# clock.net
KiCad netlist of a schematic drawn in Altium Designer
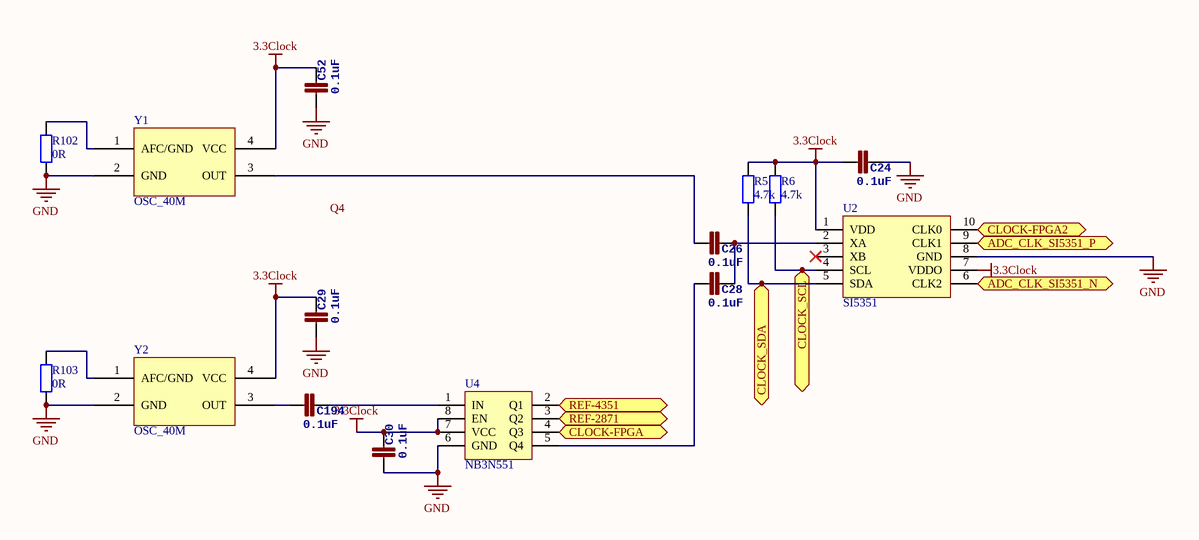
[diagram p0: clock.SchDoc]

(export (version "E")
  (design (tool "Eeschema 10.0.6"))
  (components
    (comp (ref "C24")
      (value "0.1uF")
      (footprint "0402")
      (description "<b>Capacitor</b>\nStandard 0603 ceramic capacitor, and 0.1\" leaded capacitor.")
      (fields (field (name "PARTNO") "CC0402ZRY5V7BB104"))
      (libsource (lib "pixhawk2") (part "CAP0402-CAP"))
    )
    (comp (ref "C26")
      (value "0.1uF")
      (footprint "0402")
      (description "<b>Capacitor</b>\nStandard 0603 ceramic capacitor, and 0.1\" leaded capacitor.")
      (fields (field (name "PARTNO") "CC0402ZRY5V7BB104"))
      (libsource (lib "pixhawk2") (part "CAP0402-CAP"))
    )
    (comp (ref "C28")
      (value "0.1uF")
      (footprint "0402")
      (description "<b>Capacitor</b>\nStandard 0603 ceramic capacitor, and 0.1\" leaded capacitor.")
      (fields (field (name "PARTNO") "CC0402ZRY5V7BB104"))
      (libsource (lib "pixhawk2") (part "CAP0402-CAP"))
    )
    (comp (ref "C29")
      (value "0.1uF")
      (footprint "0402")
      (description "<b>Capacitor</b>\nStandard 0603 ceramic capacitor, and 0.1\" leaded capacitor.")
      (fields (field (name "PARTNO") "CC0402ZRY5V7BB104"))
      (libsource (lib "") (part "CAP0402-CAP_1"))
    )
    (comp (ref "C30")
      (value "0.1uF")
      (footprint "0402")
      (description "<b>Capacitor</b>\nStandard 0603 ceramic capacitor, and 0.1\" leaded capacitor.")
      (fields (field (name "PARTNO") "CC0402ZRY5V7BB104"))
      (libsource (lib "") (part "CAP0402-CAP_1"))
    )
    (comp (ref "C52")
      (value "0.1uF")
      (footprint "0402")
      (description "<b>Capacitor</b>\nStandard 0603 ceramic capacitor, and 0.1\" leaded capacitor.")
      (fields (field (name "PARTNO") "CC0402ZRY5V7BB104"))
      (libsource (lib "") (part "CAP0402-CAP_1"))
    )
    (comp (ref "C194")
      (value "0.1uF")
      (footprint "0402")
      (description "<b>Capacitor</b>\nStandard 0603 ceramic capacitor, and 0.1\" leaded capacitor.")
      (fields (field (name "PARTNO") "CC0402ZRY5V7BB104"))
      (libsource (lib "pixhawk2") (part "CAP0402-CAP"))
    )
    (comp (ref "R5")
      (value "4.7k")
      (footprint "0402")
      (description "Resistor")
      (fields (field (name "PUBLISHER") "Altium Limited"))
      (libsource (lib "Miscellaneous Devices") (part "Res2"))
    )
    (comp (ref "R6")
      (value "4.7k")
      (footprint "0402")
      (description "Resistor")
      (fields (field (name "PUBLISHER") "Altium Limited"))
      (libsource (lib "Miscellaneous Devices") (part "Res2"))
    )
    (comp (ref "R102")
      (value "0R")
      (footprint "0402")
      (description "Resistor")
      (fields (field (name "PUBLISHER") "Altium Limited"))
      (libsource (lib "Miscellaneous Devices") (part "Res2"))
    )
    (comp (ref "R103")
      (value "0R")
      (footprint "0402")
      (description "Resistor")
      (fields (field (name "PUBLISHER") "Altium Limited"))
      (libsource (lib "Miscellaneous Devices") (part "Res2"))
    )
    (comp (ref "U2") (value "SI5351") (footprint "MSOP10/VSSOP10") (libsource (lib "F4SDR") (part "SI5351")))
    (comp (ref "U4") (value "NB3N551") (footprint "SO8") (libsource (lib "F4SDR") (part "NB3N551")))
    (comp (ref "Y1") (value "OSC_40M") (footprint "TXC_7Q") (libsource (lib "F4SDR") (part "OSC_40M")))
    (comp (ref "Y2") (value "OSC_40M") (footprint "TXC_7Q") (libsource (lib "F4SDR") (part "OSC_40M")))
  )
  (nets
    (net (code "1") (name "/ADC_CLK_SI5351_N") (class "Default")
      (node (ref "U2") (pin "6") (pinfunction "CLK2_6") (pintype "passive"))
    )
    (net (code "2") (name "/ADC_CLK_SI5351_P") (class "Default")
      (node (ref "U2") (pin "9") (pinfunction "CLK1_9") (pintype "passive"))
    )
    (net (code "3") (name "/CLOCK-FPGA") (class "Default")
      (node (ref "U4") (pin "4") (pinfunction "Q3_4") (pintype "passive"))
    )
    (net (code "4") (name "/CLOCK-FPGA2") (class "Default")
      (node (ref "U2") (pin "10") (pinfunction "CLK0_10") (pintype "passive"))
    )
    (net (code "5") (name "/CLOCK_SCL") (class "Default")
      (node (ref "R6") (pin "2") (pinfunction "2_2") (pintype "passive"))
      (node (ref "U2") (pin "4") (pinfunction "SCL_4") (pintype "passive"))
    )
    (net (code "6") (name "/CLOCK_SDA") (class "Default")
      (node (ref "R5") (pin "2") (pinfunction "2_2") (pintype "passive"))
      (node (ref "U2") (pin "5") (pinfunction "SDA_5") (pintype "passive"))
    )
    (net (code "8") (name "/REF-2871") (class "Default")
      (node (ref "U4") (pin "3") (pinfunction "Q2_3") (pintype "passive"))
    )
    (net (code "9") (name "/REF-4351") (class "Default")
      (node (ref "U4") (pin "2") (pinfunction "Q1_2") (pintype "passive"))
    )
    (net (code "10") (name "3.3Clock") (class "Default")
      (node (ref "C24") (pin "1") (pinfunction "1_1") (pintype "passive"))
      (node (ref "C29") (pin "2") (pinfunction "2_2") (pintype "passive"))
      (node (ref "C30") (pin "2") (pinfunction "2_2") (pintype "passive"))
      (node (ref "C52") (pin "2") (pinfunction "2_2") (pintype "passive"))
      (node (ref "R5") (pin "1") (pinfunction "1_1") (pintype "passive"))
      (node (ref "R6") (pin "1") (pinfunction "1_1") (pintype "passive"))
      (node (ref "U2") (pin "1") (pinfunction "VDD_1") (pintype "passive"))
      (node (ref "U2") (pin "7") (pinfunction "VDDO_7") (pintype "passive"))
      (node (ref "U4") (pin "7") (pinfunction "VCC_7") (pintype "passive"))
      (node (ref "U4") (pin "8") (pinfunction "EN_8") (pintype "passive"))
      (node (ref "Y1") (pin "4") (pinfunction "VCC_4") (pintype "passive"))
      (node (ref "Y2") (pin "4") (pinfunction "VCC_4") (pintype "passive"))
    )
    (net (code "11") (name "GND") (class "Default")
      (node (ref "C24") (pin "2") (pinfunction "2_2") (pintype "passive"))
      (node (ref "C29") (pin "1") (pinfunction "1_1") (pintype "passive"))
      (node (ref "C30") (pin "1") (pinfunction "1_1") (pintype "passive"))
      (node (ref "C52") (pin "1") (pinfunction "1_1") (pintype "passive"))
      (node (ref "R102") (pin "2") (pinfunction "2_2") (pintype "passive"))
      (node (ref "R103") (pin "2") (pinfunction "2_2") (pintype "passive"))
      (node (ref "U2") (pin "8") (pinfunction "GND_8") (pintype "passive"))
      (node (ref "U4") (pin "6") (pinfunction "GND_6") (pintype "passive"))
      (node (ref "Y1") (pin "2") (pinfunction "GND_2") (pintype "passive"))
      (node (ref "Y2") (pin "2") (pinfunction "GND_2") (pintype "passive"))
    )
    (net (code "12") (name "Net-(U2-XA)") (class "Default")
      (node (ref "C26") (pin "2") (pinfunction "2_2") (pintype "passive"))
      (node (ref "C28") (pin "2") (pinfunction "2_2") (pintype "passive"))
      (node (ref "U2") (pin "2") (pinfunction "XA_2") (pintype "passive"))
    )
    (net (code "13") (name "Net-(U4-IN)") (class "Default")
      (node (ref "C194") (pin "2") (pinfunction "2_2") (pintype "passive"))
      (node (ref "U4") (pin "1") (pinfunction "IN_1") (pintype "passive"))
    )
    (net (code "14") (name "Net-(U4-Q4)") (class "Default")
      (node (ref "C28") (pin "1") (pinfunction "1_1") (pintype "passive"))
      (node (ref "U4") (pin "5") (pinfunction "Q4_5") (pintype "passive"))
    )
    (net (code "15") (name "Net-(Y1-AFC{slash}GND)") (class "Default")
      (node (ref "R102") (pin "1") (pinfunction "1_1") (pintype "passive"))
      (node (ref "Y1") (pin "1") (pinfunction "AFC/GND_1") (pintype "passive"))
    )
    (net (code "16") (name "Net-(Y1-OUT)") (class "Default")
      (node (ref "C26") (pin "1") (pinfunction "1_1") (pintype "passive"))
      (node (ref "Y1") (pin "3") (pinfunction "OUT_3") (pintype "passive"))
    )
    (net (code "17") (name "Net-(Y2-AFC{slash}GND)") (class "Default")
      (node (ref "R103") (pin "1") (pinfunction "1_1") (pintype "passive"))
      (node (ref "Y2") (pin "1") (pinfunction "AFC/GND_1") (pintype "passive"))
    )
    (net (code "18") (name "Net-(Y2-OUT)") (class "Default")
      (node (ref "C194") (pin "1") (pinfunction "1_1") (pintype "passive"))
      (node (ref "Y2") (pin "3") (pinfunction "OUT_3") (pintype "passive"))
    )
    (net (code "19") (name "unconnected-(U2-XB-Pad3)") (class "Default")
      (node (ref "U2") (pin "3") (pinfunction "XB_3") (pintype "passive+no_connect"))
    )
  )
)
